# LaserXSegment.net
KiCad netlist of a schematic drawn in EAGLE
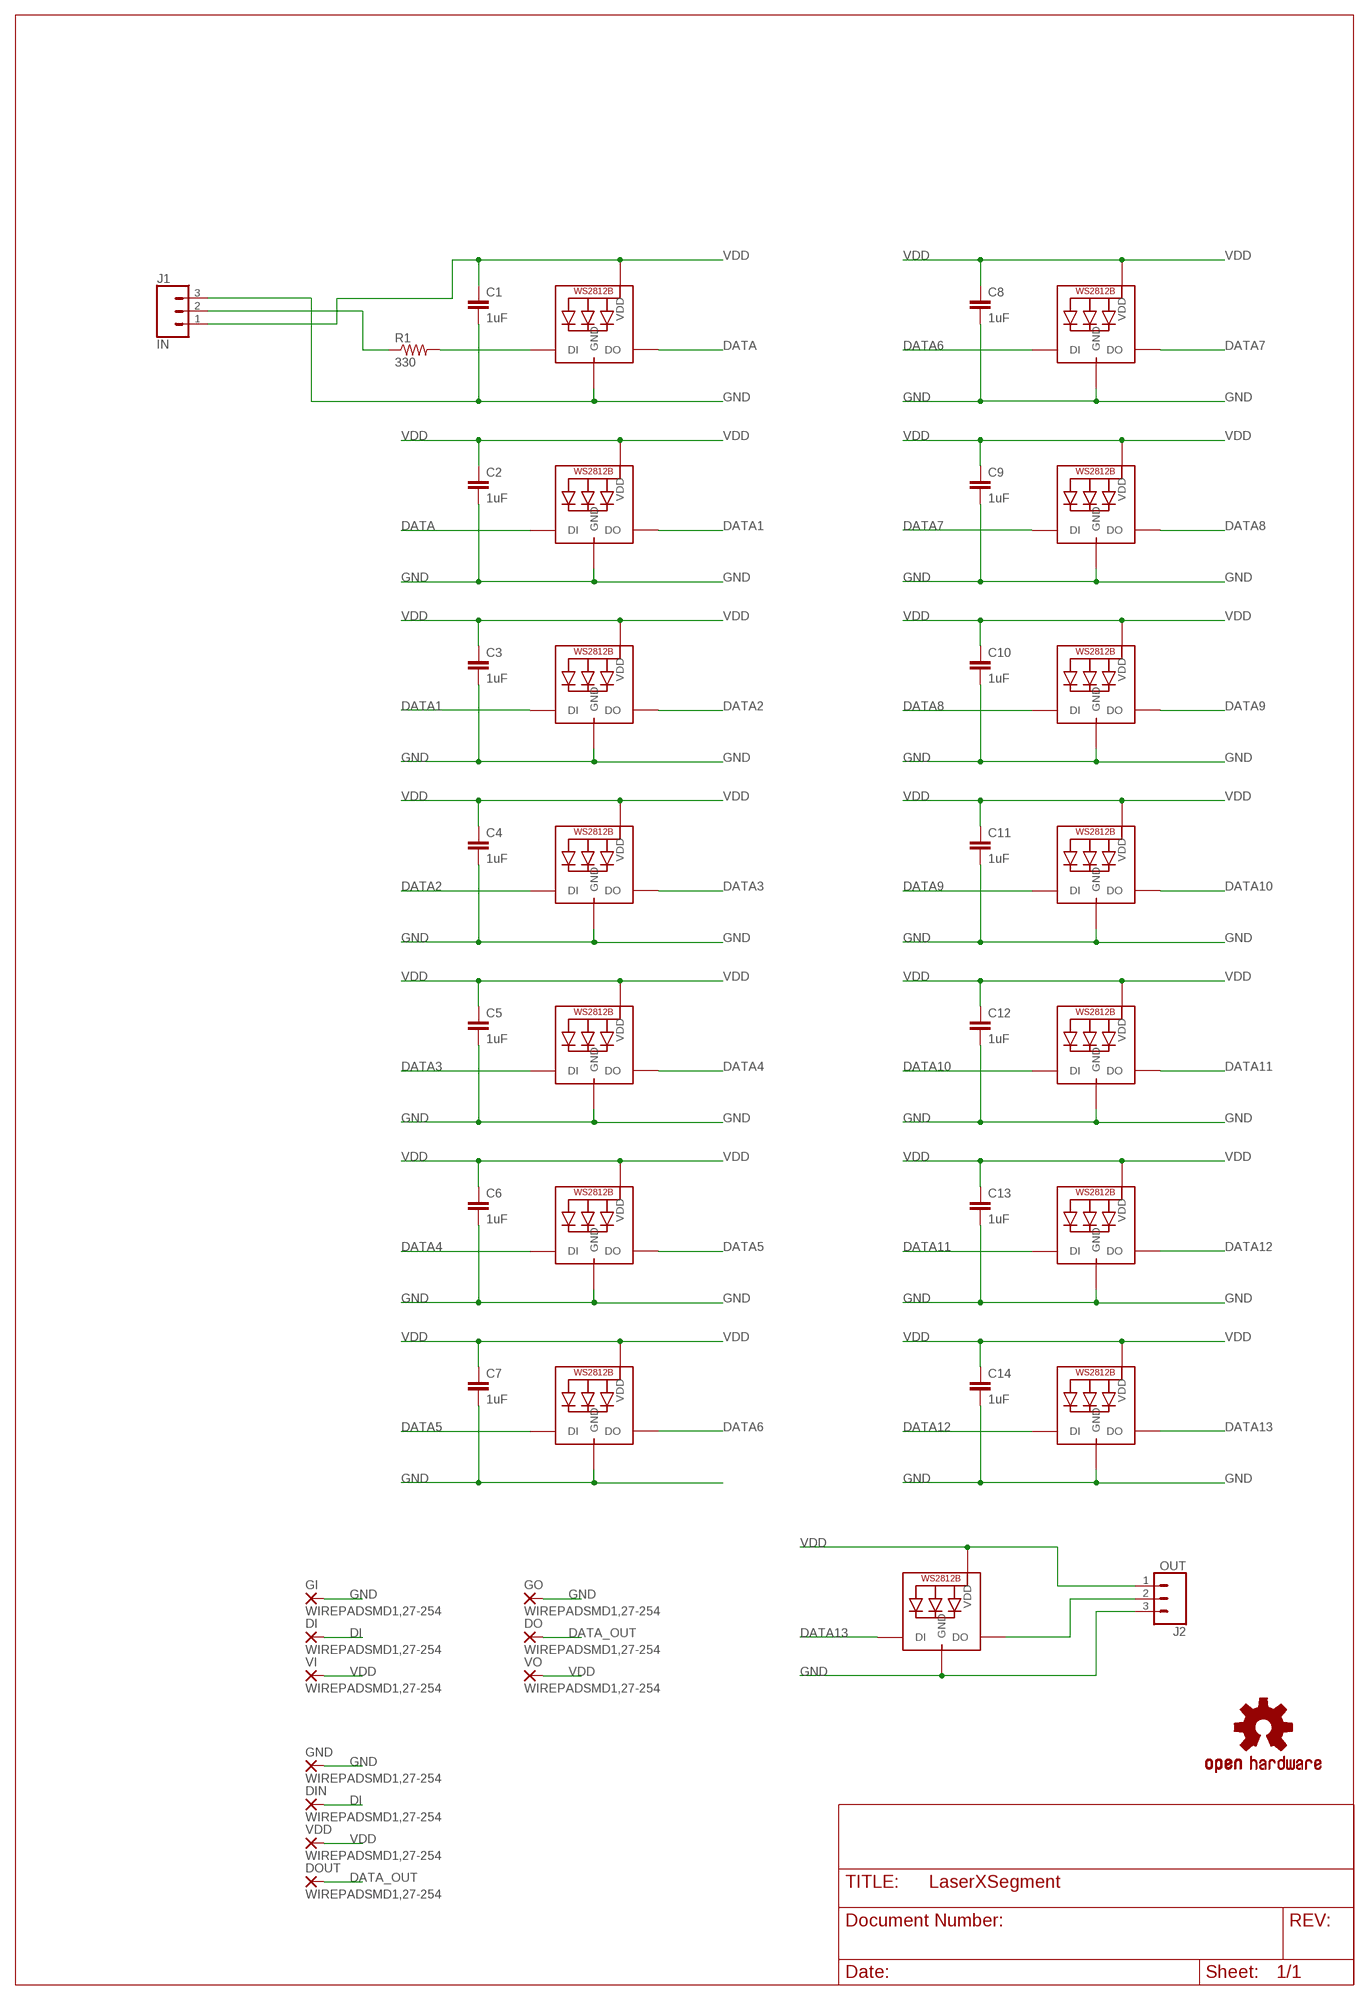
[diagram p0: schematic, sheet 1]

(export (version "E")
  (design (tool "Eeschema 10.0.6"))
  (components
    (comp (ref "C1")
      (value "1uF")
      (footprint "eagle-import:C0805")
      (libsource (lib "eagle-import") (part "C-EUC0805"))
    )
    (comp (ref "C2")
      (value "1uF")
      (footprint "eagle-import:C0805")
      (libsource (lib "eagle-import") (part "C-EUC0805"))
    )
    (comp (ref "C3")
      (value "1uF")
      (footprint "eagle-import:C0805")
      (libsource (lib "eagle-import") (part "C-EUC0805"))
    )
    (comp (ref "C4")
      (value "1uF")
      (footprint "eagle-import:C0805")
      (libsource (lib "eagle-import") (part "C-EUC0805"))
    )
    (comp (ref "C5")
      (value "1uF")
      (footprint "eagle-import:C0805")
      (libsource (lib "eagle-import") (part "C-EUC0805"))
    )
    (comp (ref "C6")
      (value "1uF")
      (footprint "eagle-import:C0805")
      (libsource (lib "eagle-import") (part "C-EUC0805"))
    )
    (comp (ref "C7")
      (value "1uF")
      (footprint "eagle-import:C0805")
      (libsource (lib "eagle-import") (part "C-EUC0805"))
    )
    (comp (ref "C8")
      (value "1uF")
      (footprint "eagle-import:C0805")
      (libsource (lib "eagle-import") (part "C-EUC0805"))
    )
    (comp (ref "C9")
      (value "1uF")
      (footprint "eagle-import:C0805")
      (libsource (lib "eagle-import") (part "C-EUC0805"))
    )
    (comp (ref "C10")
      (value "1uF")
      (footprint "eagle-import:C0805")
      (libsource (lib "eagle-import") (part "C-EUC0805"))
    )
    (comp (ref "C11")
      (value "1uF")
      (footprint "eagle-import:C0805")
      (libsource (lib "eagle-import") (part "C-EUC0805"))
    )
    (comp (ref "C12")
      (value "1uF")
      (footprint "eagle-import:C0805")
      (libsource (lib "eagle-import") (part "C-EUC0805"))
    )
    (comp (ref "C13")
      (value "1uF")
      (footprint "eagle-import:C0805")
      (libsource (lib "eagle-import") (part "C-EUC0805"))
    )
    (comp (ref "C14")
      (value "1uF")
      (footprint "eagle-import:C0805")
      (libsource (lib "eagle-import") (part "C-EUC0805"))
    )
    (comp (ref "DI")
      (value "WIREPADSMD1,27-254")
      (footprint "eagle-import:SMD1,27-2,54")
      (libsource (lib "eagle-import") (part "WIREPADSMD1,27-254"))
    )
    (comp (ref "DIN")
      (value "WIREPADSMD1,27-254")
      (footprint "eagle-import:SMD1,27-2,54")
      (libsource (lib "eagle-import") (part "WIREPADSMD1,27-254"))
    )
    (comp (ref "DO")
      (value "WIREPADSMD1,27-254")
      (footprint "eagle-import:SMD1,27-2,54")
      (libsource (lib "eagle-import") (part "WIREPADSMD1,27-254"))
    )
    (comp (ref "DOUT")
      (value "WIREPADSMD1,27-254")
      (footprint "eagle-import:SMD1,27-2,54")
      (libsource (lib "eagle-import") (part "WIREPADSMD1,27-254"))
    )
    (comp (ref "GI")
      (value "WIREPADSMD1,27-254")
      (footprint "eagle-import:SMD1,27-2,54")
      (libsource (lib "eagle-import") (part "WIREPADSMD1,27-254"))
    )
    (comp (ref "GND")
      (value "WIREPADSMD1,27-254")
      (footprint "eagle-import:SMD1,27-2,54")
      (libsource (lib "eagle-import") (part "WIREPADSMD1,27-254"))
    )
    (comp (ref "GO")
      (value "WIREPADSMD1,27-254")
      (footprint "eagle-import:SMD1,27-2,54")
      (libsource (lib "eagle-import") (part "WIREPADSMD1,27-254"))
    )
    (comp (ref "J1")
      (value "IN")
      (footprint "eagle-import:1X03_LONGPADS")
      (libsource (lib "eagle-import") (part "CONN_03LONGPADS"))
    )
    (comp (ref "J2")
      (value "OUT")
      (footprint "eagle-import:1X03_LONGPADS")
      (libsource (lib "eagle-import") (part "CONN_03LONGPADS"))
    )
    (comp (ref "L1")
      (value "WS2812B5050")
      (footprint "eagle-import:WS2812B")
      (libsource (lib "eagle-import") (part "WS2812B5050"))
    )
    (comp (ref "L2")
      (value "WS2812B5050")
      (footprint "eagle-import:WS2812B")
      (libsource (lib "eagle-import") (part "WS2812B5050"))
    )
    (comp (ref "L3")
      (value "WS2812B5050")
      (footprint "eagle-import:WS2812B")
      (libsource (lib "eagle-import") (part "WS2812B5050"))
    )
    (comp (ref "L4")
      (value "WS2812B5050")
      (footprint "eagle-import:WS2812B")
      (libsource (lib "eagle-import") (part "WS2812B5050"))
    )
    (comp (ref "L5")
      (value "WS2812B5050")
      (footprint "eagle-import:WS2812B")
      (libsource (lib "eagle-import") (part "WS2812B5050"))
    )
    (comp (ref "L6")
      (value "WS2812B5050")
      (footprint "eagle-import:WS2812B")
      (libsource (lib "eagle-import") (part "WS2812B5050"))
    )
    (comp (ref "L7")
      (value "WS2812B5050")
      (footprint "eagle-import:WS2812B")
      (libsource (lib "eagle-import") (part "WS2812B5050"))
    )
    (comp (ref "L8")
      (value "WS2812B5050")
      (footprint "eagle-import:WS2812B")
      (libsource (lib "eagle-import") (part "WS2812B5050"))
    )
    (comp (ref "L9")
      (value "WS2812B5050")
      (footprint "eagle-import:WS2812B")
      (libsource (lib "eagle-import") (part "WS2812B5050"))
    )
    (comp (ref "L10")
      (value "WS2812B5050")
      (footprint "eagle-import:WS2812B")
      (libsource (lib "eagle-import") (part "WS2812B5050"))
    )
    (comp (ref "L11")
      (value "WS2812B5050")
      (footprint "eagle-import:WS2812B")
      (libsource (lib "eagle-import") (part "WS2812B5050"))
    )
    (comp (ref "L12")
      (value "WS2812B5050")
      (footprint "eagle-import:WS2812B")
      (libsource (lib "eagle-import") (part "WS2812B5050"))
    )
    (comp (ref "L13")
      (value "WS2812B5050")
      (footprint "eagle-import:WS2812B")
      (libsource (lib "eagle-import") (part "WS2812B5050"))
    )
    (comp (ref "L14")
      (value "WS2812B5050")
      (footprint "eagle-import:WS2812B")
      (libsource (lib "eagle-import") (part "WS2812B5050"))
    )
    (comp (ref "L15")
      (value "RGB 3535")
      (footprint "eagle-import:LED3535")
      (libsource (lib "eagle-import") (part "WS2812B3535"))
    )
    (comp (ref "LOGO1")
      (value "OSHW-LOGOM")
      (footprint "eagle-import:OSHW-LOGO-M")
      (libsource (lib "eagle-import") (part "OSHW-LOGOM"))
    )
    (comp (ref "R1")
      (value "330")
      (footprint "eagle-import:R0805")
      (libsource (lib "eagle-import") (part "R-US_R0805"))
    )
    (comp (ref "VDD")
      (value "WIREPADSMD1,27-254")
      (footprint "eagle-import:SMD1,27-2,54")
      (libsource (lib "eagle-import") (part "WIREPADSMD1,27-254"))
    )
    (comp (ref "VI")
      (value "WIREPADSMD1,27-254")
      (footprint "eagle-import:SMD1,27-2,54")
      (libsource (lib "eagle-import") (part "WIREPADSMD1,27-254"))
    )
    (comp (ref "VO")
      (value "WIREPADSMD1,27-254")
      (footprint "eagle-import:SMD1,27-2,54")
      (libsource (lib "eagle-import") (part "WIREPADSMD1,27-254"))
    )
  )
  (nets
    (net (code "1") (name "/DATA") (class "Default")
      (node (ref "L1") (pin "2-DOUT") (pinfunction "DO_2-DOUT") (pintype "output"))
      (node (ref "L2") (pin "4-DIN") (pinfunction "DI_4-DIN") (pintype "input"))
    )
    (net (code "2") (name "/DATA1") (class "Default")
      (node (ref "L2") (pin "2-DOUT") (pinfunction "DO_2-DOUT") (pintype "output"))
      (node (ref "L3") (pin "4-DIN") (pinfunction "DI_4-DIN") (pintype "input"))
    )
    (net (code "3") (name "/DATA2") (class "Default")
      (node (ref "L3") (pin "2-DOUT") (pinfunction "DO_2-DOUT") (pintype "output"))
      (node (ref "L4") (pin "4-DIN") (pinfunction "DI_4-DIN") (pintype "input"))
    )
    (net (code "4") (name "/DATA3") (class "Default")
      (node (ref "L4") (pin "2-DOUT") (pinfunction "DO_2-DOUT") (pintype "output"))
      (node (ref "L5") (pin "4-DIN") (pinfunction "DI_4-DIN") (pintype "input"))
    )
    (net (code "5") (name "/DATA4") (class "Default")
      (node (ref "L5") (pin "2-DOUT") (pinfunction "DO_2-DOUT") (pintype "output"))
      (node (ref "L6") (pin "4-DIN") (pinfunction "DI_4-DIN") (pintype "input"))
    )
    (net (code "6") (name "/DATA5") (class "Default")
      (node (ref "L6") (pin "2-DOUT") (pinfunction "DO_2-DOUT") (pintype "output"))
      (node (ref "L7") (pin "4-DIN") (pinfunction "DI_4-DIN") (pintype "input"))
    )
    (net (code "7") (name "/DATA6") (class "Default")
      (node (ref "L7") (pin "2-DOUT") (pinfunction "DO_2-DOUT") (pintype "output"))
      (node (ref "L8") (pin "4-DIN") (pinfunction "DI_4-DIN") (pintype "input"))
    )
    (net (code "8") (name "/DATA7") (class "Default")
      (node (ref "L8") (pin "2-DOUT") (pinfunction "DO_2-DOUT") (pintype "output"))
      (node (ref "L9") (pin "4-DIN") (pinfunction "DI_4-DIN") (pintype "input"))
    )
    (net (code "9") (name "/DATA8") (class "Default")
      (node (ref "L10") (pin "4-DIN") (pinfunction "DI_4-DIN") (pintype "input"))
      (node (ref "L9") (pin "2-DOUT") (pinfunction "DO_2-DOUT") (pintype "output"))
    )
    (net (code "10") (name "/DATA9") (class "Default")
      (node (ref "L10") (pin "2-DOUT") (pinfunction "DO_2-DOUT") (pintype "output"))
      (node (ref "L11") (pin "4-DIN") (pinfunction "DI_4-DIN") (pintype "input"))
    )
    (net (code "11") (name "/DATA10") (class "Default")
      (node (ref "L11") (pin "2-DOUT") (pinfunction "DO_2-DOUT") (pintype "output"))
      (node (ref "L12") (pin "4-DIN") (pinfunction "DI_4-DIN") (pintype "input"))
    )
    (net (code "12") (name "/DATA11") (class "Default")
      (node (ref "L12") (pin "2-DOUT") (pinfunction "DO_2-DOUT") (pintype "output"))
      (node (ref "L13") (pin "4-DIN") (pinfunction "DI_4-DIN") (pintype "input"))
    )
    (net (code "13") (name "/DATA12") (class "Default")
      (node (ref "L13") (pin "2-DOUT") (pinfunction "DO_2-DOUT") (pintype "output"))
      (node (ref "L14") (pin "4-DIN") (pinfunction "DI_4-DIN") (pintype "input"))
    )
    (net (code "14") (name "/DATA13") (class "Default")
      (node (ref "L14") (pin "2-DOUT") (pinfunction "DO_2-DOUT") (pintype "output"))
      (node (ref "L15") (pin "1") (pinfunction "DI_1") (pintype "input"))
    )
    (net (code "15") (name "/DATA_OUT") (class "Default")
      (node (ref "DO") (pin "1") (pinfunction "P_1") (pintype "passive"))
      (node (ref "DOUT") (pin "1") (pinfunction "P_1") (pintype "passive"))
      (node (ref "J2") (pin "2") (pinfunction "2_2") (pintype "passive"))
      (node (ref "L15") (pin "3") (pinfunction "DO_3") (pintype "output"))
    )
    (net (code "16") (name "/DI") (class "Default")
      (node (ref "DI") (pin "1") (pinfunction "P_1") (pintype "passive"))
      (node (ref "DIN") (pin "1") (pinfunction "P_1") (pintype "passive"))
      (node (ref "J1") (pin "2") (pinfunction "2_2") (pintype "passive"))
      (node (ref "R1") (pin "1") (pinfunction "1_1") (pintype "passive"))
    )
    (net (code "17") (name "/GND") (class "Default")
      (node (ref "C1") (pin "2") (pinfunction "2_2") (pintype "passive"))
      (node (ref "C10") (pin "2") (pinfunction "2_2") (pintype "passive"))
      (node (ref "C11") (pin "2") (pinfunction "2_2") (pintype "passive"))
      (node (ref "C12") (pin "2") (pinfunction "2_2") (pintype "passive"))
      (node (ref "C13") (pin "2") (pinfunction "2_2") (pintype "passive"))
      (node (ref "C14") (pin "2") (pinfunction "2_2") (pintype "passive"))
      (node (ref "C2") (pin "2") (pinfunction "2_2") (pintype "passive"))
      (node (ref "C3") (pin "2") (pinfunction "2_2") (pintype "passive"))
      (node (ref "C4") (pin "2") (pinfunction "2_2") (pintype "passive"))
      (node (ref "C5") (pin "2") (pinfunction "2_2") (pintype "passive"))
      (node (ref "C6") (pin "2") (pinfunction "2_2") (pintype "passive"))
      (node (ref "C7") (pin "2") (pinfunction "2_2") (pintype "passive"))
      (node (ref "C8") (pin "2") (pinfunction "2_2") (pintype "passive"))
      (node (ref "C9") (pin "2") (pinfunction "2_2") (pintype "passive"))
      (node (ref "GI") (pin "1") (pinfunction "P_1") (pintype "passive"))
      (node (ref "GND") (pin "1") (pinfunction "P_1") (pintype "passive"))
      (node (ref "GO") (pin "1") (pinfunction "P_1") (pintype "passive"))
      (node (ref "J1") (pin "3") (pinfunction "3_3") (pintype "passive"))
      (node (ref "J2") (pin "3") (pinfunction "3_3") (pintype "passive"))
      (node (ref "L1") (pin "3-GND") (pinfunction "GND_3-GND") (pintype "power_in"))
      (node (ref "L10") (pin "3-GND") (pinfunction "GND_3-GND") (pintype "power_in"))
      (node (ref "L11") (pin "3-GND") (pinfunction "GND_3-GND") (pintype "power_in"))
      (node (ref "L12") (pin "3-GND") (pinfunction "GND_3-GND") (pintype "power_in"))
      (node (ref "L13") (pin "3-GND") (pinfunction "GND_3-GND") (pintype "power_in"))
      (node (ref "L14") (pin "3-GND") (pinfunction "GND_3-GND") (pintype "power_in"))
      (node (ref "L15") (pin "4") (pinfunction "GND_4") (pintype "power_in"))
      (node (ref "L2") (pin "3-GND") (pinfunction "GND_3-GND") (pintype "power_in"))
      (node (ref "L3") (pin "3-GND") (pinfunction "GND_3-GND") (pintype "power_in"))
      (node (ref "L4") (pin "3-GND") (pinfunction "GND_3-GND") (pintype "power_in"))
      (node (ref "L5") (pin "3-GND") (pinfunction "GND_3-GND") (pintype "power_in"))
      (node (ref "L6") (pin "3-GND") (pinfunction "GND_3-GND") (pintype "power_in"))
      (node (ref "L7") (pin "3-GND") (pinfunction "GND_3-GND") (pintype "power_in"))
      (node (ref "L8") (pin "3-GND") (pinfunction "GND_3-GND") (pintype "power_in"))
      (node (ref "L9") (pin "3-GND") (pinfunction "GND_3-GND") (pintype "power_in"))
    )
    (net (code "18") (name "/VDD") (class "Default")
      (node (ref "C1") (pin "1") (pinfunction "1_1") (pintype "passive"))
      (node (ref "C10") (pin "1") (pinfunction "1_1") (pintype "passive"))
      (node (ref "C11") (pin "1") (pinfunction "1_1") (pintype "passive"))
      (node (ref "C12") (pin "1") (pinfunction "1_1") (pintype "passive"))
      (node (ref "C13") (pin "1") (pinfunction "1_1") (pintype "passive"))
      (node (ref "C14") (pin "1") (pinfunction "1_1") (pintype "passive"))
      (node (ref "C2") (pin "1") (pinfunction "1_1") (pintype "passive"))
      (node (ref "C3") (pin "1") (pinfunction "1_1") (pintype "passive"))
      (node (ref "C4") (pin "1") (pinfunction "1_1") (pintype "passive"))
      (node (ref "C5") (pin "1") (pinfunction "1_1") (pintype "passive"))
      (node (ref "C6") (pin "1") (pinfunction "1_1") (pintype "passive"))
      (node (ref "C7") (pin "1") (pinfunction "1_1") (pintype "passive"))
      (node (ref "C8") (pin "1") (pinfunction "1_1") (pintype "passive"))
      (node (ref "C9") (pin "1") (pinfunction "1_1") (pintype "passive"))
      (node (ref "J1") (pin "1") (pinfunction "1_1") (pintype "passive"))
      (node (ref "J2") (pin "1") (pinfunction "1_1") (pintype "passive"))
      (node (ref "L1") (pin "1-VDD") (pinfunction "VDD_1-VDD") (pintype "power_in"))
      (node (ref "L10") (pin "1-VDD") (pinfunction "VDD_1-VDD") (pintype "power_in"))
      (node (ref "L11") (pin "1-VDD") (pinfunction "VDD_1-VDD") (pintype "power_in"))
      (node (ref "L12") (pin "1-VDD") (pinfunction "VDD_1-VDD") (pintype "power_in"))
      (node (ref "L13") (pin "1-VDD") (pinfunction "VDD_1-VDD") (pintype "power_in"))
      (node (ref "L14") (pin "1-VDD") (pinfunction "VDD_1-VDD") (pintype "power_in"))
      (node (ref "L15") (pin "2") (pinfunction "VDD_2") (pintype "power_in"))
      (node (ref "L2") (pin "1-VDD") (pinfunction "VDD_1-VDD") (pintype "power_in"))
      (node (ref "L3") (pin "1-VDD") (pinfunction "VDD_1-VDD") (pintype "power_in"))
      (node (ref "L4") (pin "1-VDD") (pinfunction "VDD_1-VDD") (pintype "power_in"))
      (node (ref "L5") (pin "1-VDD") (pinfunction "VDD_1-VDD") (pintype "power_in"))
      (node (ref "L6") (pin "1-VDD") (pinfunction "VDD_1-VDD") (pintype "power_in"))
      (node (ref "L7") (pin "1-VDD") (pinfunction "VDD_1-VDD") (pintype "power_in"))
      (node (ref "L8") (pin "1-VDD") (pinfunction "VDD_1-VDD") (pintype "power_in"))
      (node (ref "L9") (pin "1-VDD") (pinfunction "VDD_1-VDD") (pintype "power_in"))
      (node (ref "VDD") (pin "1") (pinfunction "P_1") (pintype "passive"))
      (node (ref "VI") (pin "1") (pinfunction "P_1") (pintype "passive"))
      (node (ref "VO") (pin "1") (pinfunction "P_1") (pintype "passive"))
    )
    (net (code "19") (name "Net-(L1-DI)") (class "Default")
      (node (ref "L1") (pin "4-DIN") (pinfunction "DI_4-DIN") (pintype "input"))
      (node (ref "R1") (pin "2") (pinfunction "2_2") (pintype "passive"))
    )
  )
)
